# 5VAC-DC.net
KiCad netlist of a schematic drawn in EAGLE
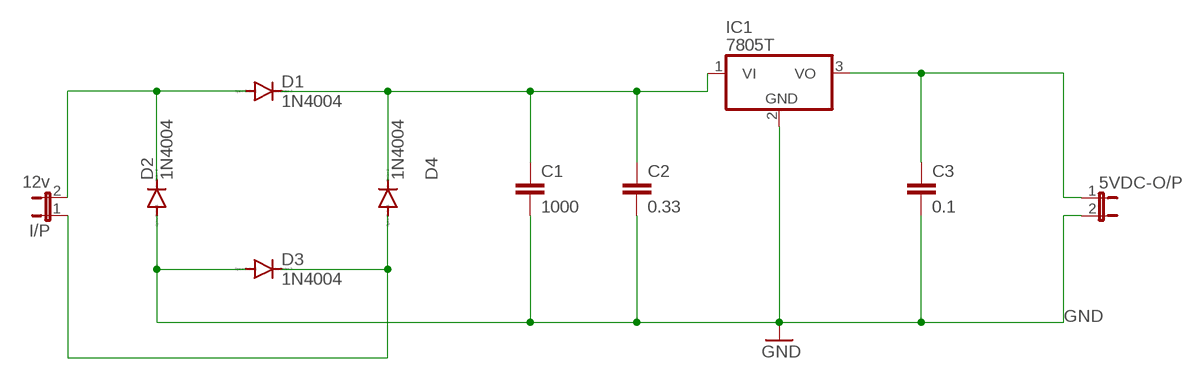
[diagram p0: schematic, sheet 1]

(export (version "E")
  (design (tool "Eeschema 10.0.6"))
  (components
    (comp (ref "5VDC-O/P")
      (value "JP1E")
      (footprint "eagle-import:JP1")
      (libsource (lib "eagle-import") (part "JP1E"))
    )
    (comp (ref "C1")
      (value "1000")
      (footprint "eagle-import:C2.5-3")
      (libsource (lib "eagle-import") (part "C2,5-3"))
    )
    (comp (ref "C2")
      (value "0.33")
      (footprint "eagle-import:C2.5-3")
      (libsource (lib "eagle-import") (part "C2,5-3"))
    )
    (comp (ref "C3")
      (value "0.1")
      (footprint "eagle-import:C2.5-3")
      (libsource (lib "eagle-import") (part "C2,5-3"))
    )
    (comp (ref "D1")
      (value "1N4004")
      (footprint "eagle-import:DO41-10")
      (libsource (lib "eagle-import") (part "1N4004"))
    )
    (comp (ref "D2")
      (value "1N4004")
      (footprint "eagle-import:DO41-10")
      (libsource (lib "eagle-import") (part "1N4004"))
    )
    (comp (ref "D3")
      (value "1N4004")
      (footprint "eagle-import:DO41-10")
      (libsource (lib "eagle-import") (part "1N4004"))
    )
    (comp (ref "D4")
      (value "1N4004")
      (footprint "eagle-import:DO41-10")
      (libsource (lib "eagle-import") (part "1N4004"))
    )
    (comp (ref "I/P")
      (value "12v")
      (footprint "eagle-import:JP1")
      (libsource (lib "eagle-import") (part "JP1E"))
    )
    (comp (ref "IC1")
      (value "7805T")
      (footprint "eagle-import:TO220H")
      (libsource (lib "eagle-import") (part "78T05"))
    )
  )
  (nets
    (net (code "1") (name "GND") (class "Default")
      (node (ref "5VDC-O/P") (pin "2") (pinfunction "2_2") (pintype "passive"))
      (node (ref "C1") (pin "2") (pinfunction "2_2") (pintype "passive"))
      (node (ref "C2") (pin "2") (pinfunction "2_2") (pintype "passive"))
      (node (ref "C3") (pin "2") (pinfunction "2_2") (pintype "passive"))
      (node (ref "D2") (pin "A") (pinfunction "A_A") (pintype "passive"))
      (node (ref "D3") (pin "A") (pinfunction "A_A") (pintype "passive"))
      (node (ref "IC1") (pin "2") (pinfunction "GND_2") (pintype "passive"))
    )
    (net (code "2") (name "Net-(D1-PadA)") (class "Default")
      (node (ref "D1") (pin "A") (pinfunction "A_A") (pintype "passive"))
      (node (ref "D2") (pin "C") (pinfunction "C_C") (pintype "passive"))
      (node (ref "I/P") (pin "2") (pinfunction "2_2") (pintype "passive"))
    )
    (net (code "3") (name "Net-(D3-PadC)") (class "Default")
      (node (ref "D3") (pin "C") (pinfunction "C_C") (pintype "passive"))
      (node (ref "D4") (pin "A") (pinfunction "A_A") (pintype "passive"))
      (node (ref "I/P") (pin "1") (pinfunction "1_1") (pintype "passive"))
    )
    (net (code "4") (name "Net-(IC1-VI)") (class "Default")
      (node (ref "C1") (pin "1") (pinfunction "1_1") (pintype "passive"))
      (node (ref "C2") (pin "1") (pinfunction "1_1") (pintype "passive"))
      (node (ref "D1") (pin "C") (pinfunction "C_C") (pintype "passive"))
      (node (ref "D4") (pin "C") (pinfunction "C_C") (pintype "passive"))
      (node (ref "IC1") (pin "1") (pinfunction "VI_1") (pintype "input"))
    )
    (net (code "5") (name "Net-(IC1-VO)") (class "Default")
      (node (ref "5VDC-O/P") (pin "1") (pinfunction "1_1") (pintype "passive"))
      (node (ref "C3") (pin "1") (pinfunction "1_1") (pintype "passive"))
      (node (ref "IC1") (pin "3") (pinfunction "VO_3") (pintype "passive"))
    )
  )
)
